# CAS_2.net
KiCad netlist of a schematic drawn in Altium Designer
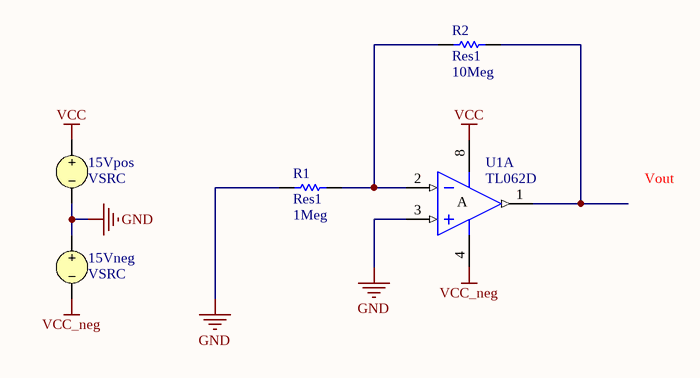
[diagram p0: CAS_2.SchDoc]

(export (version "E")
  (design (tool "Eeschema 10.0.6"))
  (components
    (comp (ref "15Vneg")
      (value "VSRC")
      (description "Voltage Source")
      (fields (field (name "PUBLISHER") "Altium Limited"))
      (libsource (lib "Simulation Generic Components") (part "VSRC"))
    )
    (comp (ref "15Vpos")
      (value "VSRC")
      (description "Voltage Source")
      (fields (field (name "PUBLISHER") "Altium Limited"))
      (libsource (lib "Simulation Generic Components") (part "VSRC"))
    )
    (comp (ref "R1")
      (value "Res1")
      (footprint "AXIAL-0.3")
      (description "Resistor")
      (fields (field (name "ALTIUM_VALUE") "1Meg") (field (name "PUBLISHER") "Altium Limited"))
      (libsource (lib "Miscellaneous Devices") (part "Res1"))
    )
    (comp (ref "R2")
      (value "Res1")
      (footprint "AXIAL-0.3")
      (description "Resistor")
      (fields (field (name "ALTIUM_VALUE") "10Meg") (field (name "PUBLISHER") "Altium Limited"))
      (libsource (lib "Miscellaneous Devices") (part "Res1"))
    )
    (comp (ref "U1")
      (value "TL062D")
      (footprint "D008_L")
      (description "Low-Power JFET-Input Operational Amplifier")
      (fields (field (name "PUBLISHER") "Altium Limited"))
      (libsource (lib "TI Operational Amplifier") (part "TL062D"))
    )
  )
  (nets
    (net (code "1") (name "GND") (class "Default")
      (node (ref "15Vneg") (pin "1") (pinfunction "1_1") (pintype "passive"))
      (node (ref "15Vpos") (pin "2") (pinfunction "2_2") (pintype "passive"))
      (node (ref "R1") (pin "1") (pinfunction "1_1") (pintype "passive"))
      (node (ref "U1") (pin "3") (pinfunction "IN+_3") (pintype "input"))
    )
    (net (code "2") (name "Net-(U1A-IN-)") (class "Default")
      (node (ref "R1") (pin "2") (pinfunction "2_2") (pintype "passive"))
      (node (ref "R2") (pin "1") (pinfunction "1_1") (pintype "passive"))
      (node (ref "U1") (pin "2") (pinfunction "IN-_2") (pintype "input"))
    )
    (net (code "3") (name "Net-(U1A-OUT)") (class "Default")
      (node (ref "R2") (pin "2") (pinfunction "2_2") (pintype "passive"))
      (node (ref "U1") (pin "1") (pinfunction "OUT_1") (pintype "output"))
    )
    (net (code "4") (name "VCC") (class "Default")
      (node (ref "15Vpos") (pin "1") (pinfunction "1_1") (pintype "passive"))
      (node (ref "U1") (pin "8") (pinfunction "V+_8") (pintype "power_in"))
    )
    (net (code "5") (name "VCC_neg") (class "Default")
      (node (ref "15Vneg") (pin "2") (pinfunction "2_2") (pintype "passive"))
      (node (ref "U1") (pin "4") (pinfunction "V-_4") (pintype "power_in"))
    )
  )
)
